# MAGI_sMicroSD_SDIO.net
KiCad netlist of a schematic drawn in Altium Designer
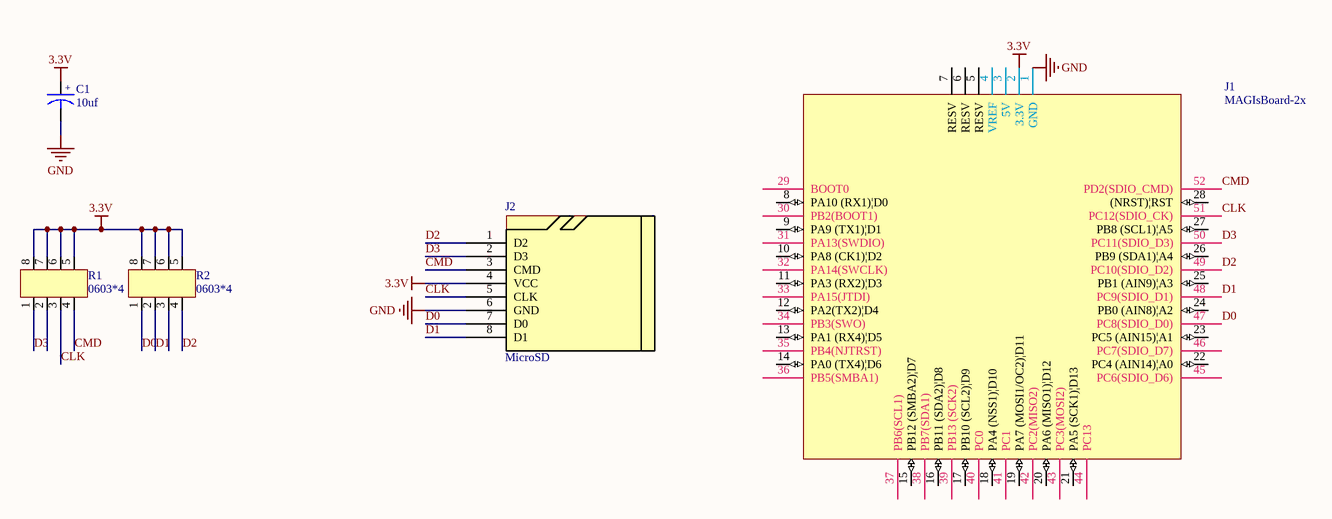
[diagram p0: MAGI'sMicroSD_SDIO.SchDoc]

(export (version "E")
  (design (tool "Eeschema 10.0.6"))
  (components
    (comp (ref "C1")
      (value "10uf")
      (footprint "6-0805_N")
      (description "Capacitor")
      (libsource (lib "电容器") (part "CAPACITOR POL"))
    )
    (comp (ref "J1")
      (value "MAGIsBoard-2x")
      (footprint "MAGIsBoard-2x")
      (libsource (lib "MAGIsBoard") (part "MAGIsBoard-2x"))
    )
    (comp (ref "J2") (value "MicroSD") (footprint "microsd") (libsource (lib "Connector") (part "MicroSD")))
    (comp (ref "R1") (value "0603*4") (footprint "0603*4") (libsource (lib "Res") (part "0603*4")))
    (comp (ref "R2") (value "0603*4") (footprint "0603*4") (libsource (lib "Res") (part "0603*4")))
  )
  (nets
    (net (code "1") (name "/CLK") (class "Default")
      (node (ref "J1") (pin "51") (pinfunction "PC12(SDIO_CK)_51") (pintype "passive"))
      (node (ref "J2") (pin "5") (pinfunction "CLK_5") (pintype "passive"))
      (node (ref "R1") (pin "3") (pintype "passive"))
    )
    (net (code "2") (name "/CMD") (class "Default")
      (node (ref "J1") (pin "52") (pinfunction "PD2(SDIO_CMD)_52") (pintype "passive"))
      (node (ref "J2") (pin "3") (pinfunction "CMD_3") (pintype "passive"))
      (node (ref "R1") (pin "4") (pintype "passive"))
    )
    (net (code "3") (name "/D0") (class "Default")
      (node (ref "J1") (pin "47") (pinfunction "PC8(SDIO_D0)_47") (pintype "passive"))
      (node (ref "J2") (pin "7") (pinfunction "D0_7") (pintype "passive"))
      (node (ref "R2") (pin "1") (pintype "passive"))
    )
    (net (code "4") (name "/D1") (class "Default")
      (node (ref "J1") (pin "48") (pinfunction "PC9(SDIO_D1)_48") (pintype "passive"))
      (node (ref "J2") (pin "8") (pinfunction "D1_8") (pintype "passive"))
      (node (ref "R2") (pin "2") (pintype "passive"))
    )
    (net (code "5") (name "/D2") (class "Default")
      (node (ref "J1") (pin "49") (pinfunction "PC10(SDIO_D2)_49") (pintype "passive"))
      (node (ref "J2") (pin "1") (pinfunction "D2_1") (pintype "passive"))
      (node (ref "R2") (pin "4") (pintype "passive"))
    )
    (net (code "6") (name "/D3") (class "Default")
      (node (ref "J1") (pin "50") (pinfunction "PC11(SDIO_D3)_50") (pintype "passive"))
      (node (ref "J2") (pin "2") (pinfunction "D3_2") (pintype "passive"))
      (node (ref "R1") (pin "1") (pintype "passive"))
    )
    (net (code "7") (name "3.3V") (class "Default")
      (node (ref "C1") (pin "1") (pinfunction "1_1") (pintype "passive"))
      (node (ref "J1") (pin "2") (pinfunction "3.3V_2") (pintype "power_in"))
      (node (ref "J2") (pin "4") (pinfunction "VCC_4") (pintype "passive"))
      (node (ref "R1") (pin "5") (pintype "passive"))
      (node (ref "R1") (pin "6") (pintype "passive"))
      (node (ref "R1") (pin "7") (pintype "passive"))
      (node (ref "R1") (pin "8") (pintype "passive"))
      (node (ref "R2") (pin "5") (pintype "passive"))
      (node (ref "R2") (pin "6") (pintype "passive"))
      (node (ref "R2") (pin "7") (pintype "passive"))
      (node (ref "R2") (pin "8") (pintype "passive"))
    )
    (net (code "8") (name "GND") (class "Default")
      (node (ref "C1") (pin "2") (pinfunction "2_2") (pintype "passive"))
      (node (ref "J1") (pin "1") (pinfunction "GND_1") (pintype "power_in"))
      (node (ref "J2") (pin "6") (pinfunction "GND_6") (pintype "passive"))
    )
    (net (code "9") (name "unconnected-(J1-(NRST)¦RST-Pad28)") (class "Default")
      (node (ref "J1") (pin "28") (pinfunction "(NRST)¦RST_28") (pintype "bidirectional"))
    )
    (net (code "10") (name "unconnected-(J1-5V-Pad3)") (class "Default")
      (node (ref "J1") (pin "3") (pinfunction "5V_3") (pintype "power_in"))
    )
    (net (code "11") (name "unconnected-(J1-BOOT0-Pad29)") (class "Default")
      (node (ref "J1") (pin "29") (pinfunction "BOOT0_29") (pintype "passive"))
    )
    (net (code "12") (name "unconnected-(J1-PA0_(TX4)¦D6-Pad14)") (class "Default")
      (node (ref "J1") (pin "14") (pinfunction "PA0_(TX4)¦D6_14") (pintype "bidirectional"))
    )
    (net (code "13") (name "unconnected-(J1-PA1_(RX4)¦D5-Pad13)") (class "Default")
      (node (ref "J1") (pin "13") (pinfunction "PA1_(RX4)¦D5_13") (pintype "bidirectional"))
    )
    (net (code "14") (name "unconnected-(J1-PA2(TX2)¦D4-Pad12)") (class "Default")
      (node (ref "J1") (pin "12") (pinfunction "PA2(TX2)¦D4_12") (pintype "bidirectional"))
    )
    (net (code "15") (name "unconnected-(J1-PA3_(RX2)¦D3-Pad11)") (class "Default")
      (node (ref "J1") (pin "11") (pinfunction "PA3_(RX2)¦D3_11") (pintype "bidirectional"))
    )
    (net (code "16") (name "unconnected-(J1-PA4_(NSS1)¦D10-Pad18)") (class "Default")
      (node (ref "J1") (pin "18") (pinfunction "PA4_(NSS1)¦D10_18") (pintype "bidirectional"))
    )
    (net (code "17") (name "unconnected-(J1-PA5_(SCK1)¦D13-Pad21)") (class "Default")
      (node (ref "J1") (pin "21") (pinfunction "PA5_(SCK1)¦D13_21") (pintype "bidirectional"))
    )
    (net (code "18") (name "unconnected-(J1-PA6_(MISO1)¦D12-Pad20)") (class "Default")
      (node (ref "J1") (pin "20") (pinfunction "PA6_(MISO1)¦D12_20") (pintype "bidirectional"))
    )
    (net (code "19") (name "unconnected-(J1-PA7_(MOSI1{slash}OC2)¦D11-Pad19)") (class "Default")
      (node (ref "J1") (pin "19") (pinfunction "PA7_(MOSI1/OC2)¦D11_19") (pintype "bidirectional"))
    )
    (net (code "20") (name "unconnected-(J1-PA8_(CK1)¦D2-Pad10)") (class "Default")
      (node (ref "J1") (pin "10") (pinfunction "PA8_(CK1)¦D2_10") (pintype "bidirectional"))
    )
    (net (code "21") (name "unconnected-(J1-PA9_(TX1)¦D1-Pad9)") (class "Default")
      (node (ref "J1") (pin "9") (pinfunction "PA9_(TX1)¦D1_9") (pintype "bidirectional"))
    )
    (net (code "22") (name "unconnected-(J1-PA10_(RX1)¦D0-Pad8)") (class "Default")
      (node (ref "J1") (pin "8") (pinfunction "PA10_(RX1)¦D0_8") (pintype "bidirectional"))
    )
    (net (code "23") (name "unconnected-(J1-PA13(SWDIO)-Pad31)") (class "Default")
      (node (ref "J1") (pin "31") (pinfunction "PA13(SWDIO)_31") (pintype "passive"))
    )
    (net (code "24") (name "unconnected-(J1-PA14(SWCLK)-Pad32)") (class "Default")
      (node (ref "J1") (pin "32") (pinfunction "PA14(SWCLK)_32") (pintype "passive"))
    )
    (net (code "25") (name "unconnected-(J1-PA15(JTDI)-Pad33)") (class "Default")
      (node (ref "J1") (pin "33") (pinfunction "PA15(JTDI)_33") (pintype "passive"))
    )
    (net (code "26") (name "unconnected-(J1-PB0_(AIN8)¦A2-Pad24)") (class "Default")
      (node (ref "J1") (pin "24") (pinfunction "PB0_(AIN8)¦A2_24") (pintype "bidirectional"))
    )
    (net (code "27") (name "unconnected-(J1-PB1_(AIN9)¦A3-Pad25)") (class "Default")
      (node (ref "J1") (pin "25") (pinfunction "PB1_(AIN9)¦A3_25") (pintype "bidirectional"))
    )
    (net (code "28") (name "unconnected-(J1-PB2(BOOT1)-Pad30)") (class "Default")
      (node (ref "J1") (pin "30") (pinfunction "PB2(BOOT1)_30") (pintype "passive"))
    )
    (net (code "29") (name "unconnected-(J1-PB3(SWO)-Pad34)") (class "Default")
      (node (ref "J1") (pin "34") (pinfunction "PB3(SWO)_34") (pintype "passive"))
    )
    (net (code "30") (name "unconnected-(J1-PB4(NJTRST)-Pad35)") (class "Default")
      (node (ref "J1") (pin "35") (pinfunction "PB4(NJTRST)_35") (pintype "passive"))
    )
    (net (code "31") (name "unconnected-(J1-PB5(SMBA1)-Pad36)") (class "Default")
      (node (ref "J1") (pin "36") (pinfunction "PB5(SMBA1)_36") (pintype "passive"))
    )
    (net (code "32") (name "unconnected-(J1-PB6(SCL1)-Pad37)") (class "Default")
      (node (ref "J1") (pin "37") (pinfunction "PB6(SCL1)_37") (pintype "passive"))
    )
    (net (code "33") (name "unconnected-(J1-PB7(SDA1)-Pad38)") (class "Default")
      (node (ref "J1") (pin "38") (pinfunction "PB7(SDA1)_38") (pintype "passive"))
    )
    (net (code "34") (name "unconnected-(J1-PB8_(SCL1)¦A5-Pad27)") (class "Default")
      (node (ref "J1") (pin "27") (pinfunction "PB8_(SCL1)¦A5_27") (pintype "bidirectional"))
    )
    (net (code "35") (name "unconnected-(J1-PB9_(SDA1)¦A4-Pad26)") (class "Default")
      (node (ref "J1") (pin "26") (pinfunction "PB9_(SDA1)¦A4_26") (pintype "bidirectional"))
    )
    (net (code "36") (name "unconnected-(J1-PB10_(SCL2)¦D9-Pad17)") (class "Default")
      (node (ref "J1") (pin "17") (pinfunction "PB10_(SCL2)¦D9_17") (pintype "bidirectional"))
    )
    (net (code "37") (name "unconnected-(J1-PB11_(SDA2)¦D8-Pad16)") (class "Default")
      (node (ref "J1") (pin "16") (pinfunction "PB11_(SDA2)¦D8_16") (pintype "bidirectional"))
    )
    (net (code "38") (name "unconnected-(J1-PB12_(SMBA2)¦D7-Pad15)") (class "Default")
      (node (ref "J1") (pin "15") (pinfunction "PB12_(SMBA2)¦D7_15") (pintype "bidirectional"))
    )
    (net (code "39") (name "unconnected-(J1-PB13_(SCK2)-Pad39)") (class "Default")
      (node (ref "J1") (pin "39") (pinfunction "PB13_(SCK2)_39") (pintype "passive"))
    )
    (net (code "40") (name "unconnected-(J1-PC0-Pad40)") (class "Default")
      (node (ref "J1") (pin "40") (pinfunction "PC0_40") (pintype "passive"))
    )
    (net (code "41") (name "unconnected-(J1-PC1-Pad41)") (class "Default")
      (node (ref "J1") (pin "41") (pinfunction "PC1_41") (pintype "passive"))
    )
    (net (code "42") (name "unconnected-(J1-PC2(MISO2)-Pad42)") (class "Default")
      (node (ref "J1") (pin "42") (pinfunction "PC2(MISO2)_42") (pintype "passive"))
    )
    (net (code "43") (name "unconnected-(J1-PC3(MOSI2)-Pad43)") (class "Default")
      (node (ref "J1") (pin "43") (pinfunction "PC3(MOSI2)_43") (pintype "passive"))
    )
    (net (code "44") (name "unconnected-(J1-PC4_(AIN14)¦A0-Pad22)") (class "Default")
      (node (ref "J1") (pin "22") (pinfunction "PC4_(AIN14)¦A0_22") (pintype "bidirectional"))
    )
    (net (code "45") (name "unconnected-(J1-PC5_(AIN15)¦A1-Pad23)") (class "Default")
      (node (ref "J1") (pin "23") (pinfunction "PC5_(AIN15)¦A1_23") (pintype "bidirectional"))
    )
    (net (code "46") (name "unconnected-(J1-PC6(SDIO_D6)-Pad45)") (class "Default")
      (node (ref "J1") (pin "45") (pinfunction "PC6(SDIO_D6)_45") (pintype "passive"))
    )
    (net (code "47") (name "unconnected-(J1-PC7(SDIO_D7)-Pad46)") (class "Default")
      (node (ref "J1") (pin "46") (pinfunction "PC7(SDIO_D7)_46") (pintype "passive"))
    )
    (net (code "48") (name "unconnected-(J1-PC13-Pad44)") (class "Default")
      (node (ref "J1") (pin "44") (pinfunction "PC13_44") (pintype "passive"))
    )
    (net (code "49") (name "unconnected-(J1-RESV-Pad5)") (class "Default")
      (node (ref "J1") (pin "5") (pinfunction "RESV_5") (pintype "passive"))
    )
    (net (code "50") (name "unconnected-(J1-RESV-Pad6)") (class "Default")
      (node (ref "J1") (pin "6") (pinfunction "RESV_6") (pintype "passive"))
    )
    (net (code "51") (name "unconnected-(J1-RESV-Pad7)") (class "Default")
      (node (ref "J1") (pin "7") (pinfunction "RESV_7") (pintype "passive"))
    )
    (net (code "52") (name "unconnected-(J1-VREF-Pad4)") (class "Default")
      (node (ref "J1") (pin "4") (pinfunction "VREF_4") (pintype "passive"))
    )
    (net (code "53") (name "unconnected-(R1-Pad2)") (class "Default")
      (node (ref "R1") (pin "2") (pintype "passive"))
    )
    (net (code "54") (name "unconnected-(R2-Pad3)") (class "Default")
      (node (ref "R2") (pin "3") (pintype "passive"))
    )
  )
)
